# H_bridge.net
KiCad netlist of a schematic drawn in Altium Designer
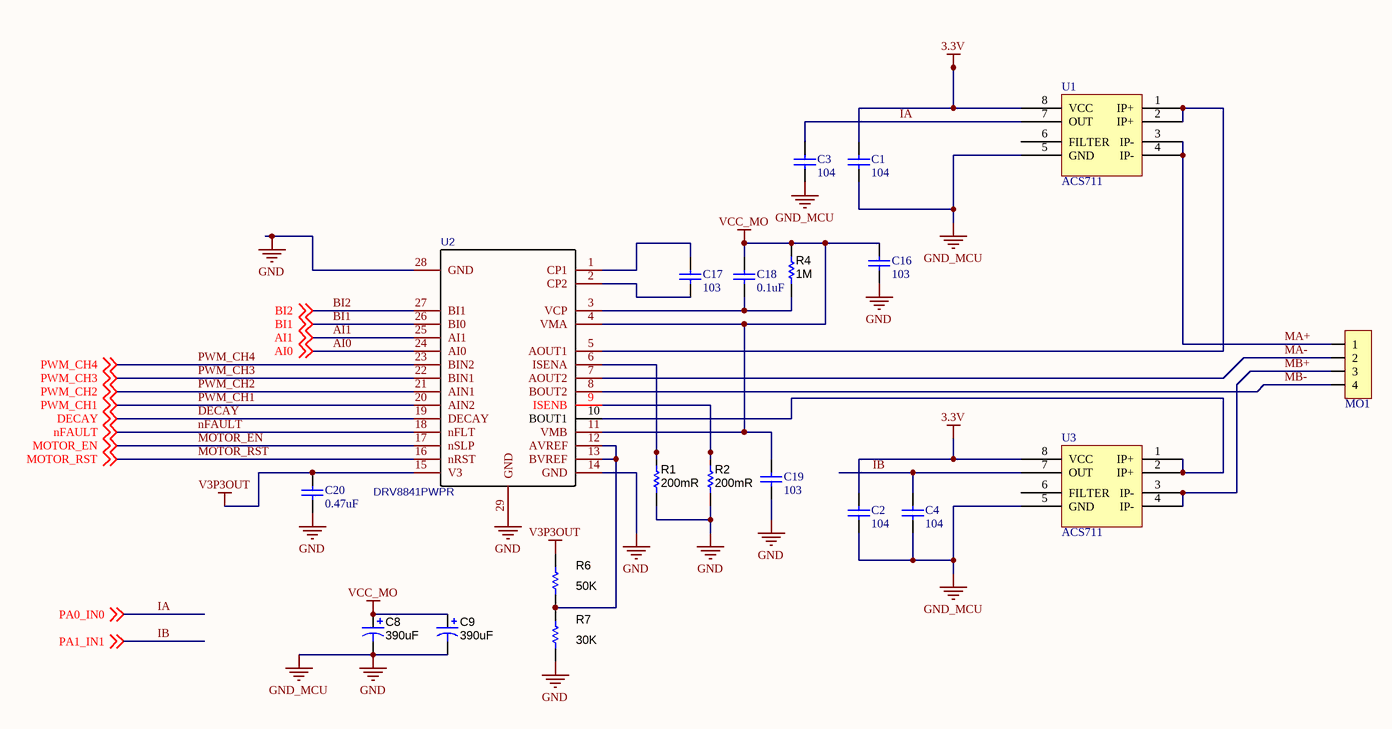
[diagram p0: H_bridge.SchDoc]

(export (version "E")
  (design (tool "Eeschema 10.0.6"))
  (components
    (comp (ref "C1")
      (value "104")
      (footprint "0805_HV")
      (description "Ceramic Chip Capacitor - Standard")
      (fields (field (name "PUBLISHER") "Altium Limited"))
      (libsource (lib "mySch") (part "Capacitor 0805"))
    )
    (comp (ref "C2")
      (value "104")
      (footprint "0805_HV")
      (description "Ceramic Chip Capacitor - Standard")
      (fields (field (name "PUBLISHER") "Altium Limited"))
      (libsource (lib "mySch") (part "Capacitor 0805"))
    )
    (comp (ref "C3")
      (value "104")
      (footprint "0805_HV")
      (description "Ceramic Chip Capacitor - Standard")
      (fields (field (name "PUBLISHER") "Altium Limited"))
      (libsource (lib "mySch") (part "Capacitor 0805"))
    )
    (comp (ref "C4")
      (value "104")
      (footprint "0805_HV")
      (description "Ceramic Chip Capacitor - Standard")
      (fields (field (name "PUBLISHER") "Altium Limited"))
      (libsource (lib "mySch") (part "Capacitor 0805"))
    )
    (comp (ref "C8")
      (value "390uF")
      (footprint "CP1/3.0")
      (fields
        (field (name "PARTNUMBER") "UHW1H391MPD6")
        (field (name "MANUFACTURER") "Nichicon")
        (field (name "VALUEDISPLAYED") "390uF")
        (field (name "PUBLISHER") "Texas Instruments")
      )
      (libsource (lib "mySch") (part "Capacitor TuHoa"))
    )
    (comp (ref "C9")
      (value "390uF")
      (footprint "CP1/3.0")
      (fields
        (field (name "PARTNUMBER") "UHW1H391MPD6")
        (field (name "MANUFACTURER") "Nichicon")
        (field (name "VALUEDISPLAYED") "390uF")
        (field (name "PUBLISHER") "Texas Instruments")
      )
      (libsource (lib "mySch") (part "Capacitor TuHoa"))
    )
    (comp (ref "C16")
      (value "103")
      (footprint "0805_HV")
      (description "Ceramic Chip Capacitor - Standard")
      (fields (field (name "PUBLISHER") "Altium Limited"))
      (libsource (lib "mySch") (part "Capacitor 0805"))
    )
    (comp (ref "C17")
      (value "103")
      (footprint "0805_HV")
      (description "Ceramic Chip Capacitor - Standard")
      (fields (field (name "PUBLISHER") "Altium Limited"))
      (libsource (lib "mySch") (part "Capacitor 0805"))
    )
    (comp (ref "C18")
      (value "0.1uF")
      (footprint "0805_HV")
      (description "Ceramic Chip Capacitor - Standard")
      (fields (field (name "PUBLISHER") "Altium Limited"))
      (libsource (lib "mySch") (part "Capacitor 0805"))
    )
    (comp (ref "C19")
      (value "103")
      (footprint "0805_HV")
      (description "Ceramic Chip Capacitor - Standard")
      (fields (field (name "PUBLISHER") "Altium Limited"))
      (libsource (lib "mySch") (part "Capacitor 0805"))
    )
    (comp (ref "C20")
      (value "0.47uF")
      (footprint "0805_HV")
      (description "Ceramic Chip Capacitor - Standard")
      (fields (field (name "PUBLISHER") "Altium Limited"))
      (libsource (lib "mySch") (part "Capacitor 0805"))
    )
    (comp (ref "MO1")
      (value "Header 4_MH")
      (footprint "HEADER 4")
      (description "Header 4P XH2.54 thẳng")
      (libsource (lib "MH_DA_THU_VIEN_16122016") (part "Header 4_MH"))
    )
    (comp (ref "R1")
      (value "RT0603DRE07140KL")
      (footprint "1210")
      (description "RES, 140 k, 0.5%, 0.1 W, 0603")
      (fields
        (field (name "VALUEDISPLAYED") "200mR")
        (field (name "MANUFACTURER") "Yageo America")
        (field (name "PUBLISHER") "Texas Instruments")
      )
      (libsource (lib "Resistor_0603") (part "RT0603DRE07140KL"))
    )
    (comp (ref "R2")
      (value "RT0603DRE07140KL")
      (footprint "1210")
      (description "RES, 140 k, 0.5%, 0.1 W, 0603")
      (fields
        (field (name "VALUEDISPLAYED") "200mR")
        (field (name "MANUFACTURER") "Yageo America")
        (field (name "PUBLISHER") "Texas Instruments")
      )
      (libsource (lib "Resistor_0603") (part "RT0603DRE07140KL"))
    )
    (comp (ref "R4")
      (value "1M")
      (footprint "0805_HV")
      (description "RES, 100, 1%, 0.1 W, 0402")
      (fields
        (field (name "PARTNUMBER") "ERJ-2RKF1000X")
        (field (name "MANUFACTURER") "Panasonic")
        (field (name "PUBLISHER") "Texas Instruments")
      )
      (libsource (lib "mySch") (part "R nho"))
    )
    (comp (ref "R6")
      (value "50K")
      (footprint "0805_HV")
      (description "RES, 100, 1%, 0.1 W, 0402")
      (fields
        (field (name "PARTNUMBER") "ERJ-2RKF1000X")
        (field (name "MANUFACTURER") "Panasonic")
        (field (name "PUBLISHER") "Texas Instruments")
      )
      (libsource (lib "mySch") (part "R nho"))
    )
    (comp (ref "R7")
      (value "30K")
      (footprint "0805_HV")
      (description "RES, 100, 1%, 0.1 W, 0402")
      (fields
        (field (name "PARTNUMBER") "ERJ-2RKF1000X")
        (field (name "MANUFACTURER") "Panasonic")
        (field (name "PUBLISHER") "Texas Instruments")
      )
      (libsource (lib "mySch") (part "R nho"))
    )
    (comp (ref "U1") (value "ACS711") (footprint "SOP 8") (libsource (lib "mySch") (part "ACS712")))
    (comp (ref "U2")
      (value "DRV8841PWPR")
      (footprint "TSSOP-28EP")
      (fields (field (name "BOM_SUPPLIER PART") "C36542"))
      (libsource (lib "Schlib1") (part "DRV8841PWPR"))
    )
    (comp (ref "U3") (value "ACS711") (footprint "SOP 8") (libsource (lib "mySch") (part "ACS712")))
  )
  (nets
    (net (code "1") (name "/MA+") (class "Default")
      (node (ref "MO1") (pin "1") (pinfunction "1_1") (pintype "passive"))
      (node (ref "U1") (pin "3") (pinfunction "IP-_3") (pintype "passive"))
      (node (ref "U1") (pin "4") (pinfunction "IP-_4") (pintype "passive"))
    )
    (net (code "2") (name "/MA-") (class "Default")
      (node (ref "MO1") (pin "2") (pinfunction "2_2") (pintype "passive"))
      (node (ref "U2") (pin "7") (pinfunction "AOUT2_7") (pintype "passive"))
    )
    (net (code "3") (name "/MB+") (class "Default")
      (node (ref "MO1") (pin "3") (pinfunction "3_3") (pintype "passive"))
      (node (ref "U3") (pin "3") (pinfunction "IP-_3") (pintype "passive"))
      (node (ref "U3") (pin "4") (pinfunction "IP-_4") (pintype "passive"))
    )
    (net (code "4") (name "/MB-") (class "Default")
      (node (ref "MO1") (pin "4") (pinfunction "4_4") (pintype "passive"))
      (node (ref "U2") (pin "8") (pinfunction "BOUT2_8") (pintype "passive"))
    )
    (net (code "5") (name "3.3V") (class "Default")
      (node (ref "C1") (pin "2") (pinfunction "2_2") (pintype "passive"))
      (node (ref "C2") (pin "2") (pinfunction "2_2") (pintype "passive"))
      (node (ref "U1") (pin "8") (pinfunction "VCC_8") (pintype "passive"))
      (node (ref "U3") (pin "8") (pinfunction "VCC_8") (pintype "passive"))
    )
    (net (code "6") (name "AI0") (class "Default")
      (node (ref "U2") (pin "24") (pinfunction "AI0_24") (pintype "passive"))
    )
    (net (code "7") (name "AI1") (class "Default")
      (node (ref "U2") (pin "25") (pinfunction "AI1_25") (pintype "passive"))
    )
    (net (code "8") (name "BI1") (class "Default")
      (node (ref "U2") (pin "26") (pinfunction "BI0_26") (pintype "passive"))
    )
    (net (code "9") (name "BI2") (class "Default")
      (node (ref "U2") (pin "27") (pinfunction "BI1_27") (pintype "passive"))
    )
    (net (code "10") (name "DECAY") (class "Default")
      (node (ref "U2") (pin "19") (pinfunction "DECAY_19") (pintype "passive"))
    )
    (net (code "11") (name "GND") (class "Default")
      (node (ref "C1") (pin "1") (pinfunction "1_1") (pintype "passive"))
      (node (ref "C16") (pin "1") (pinfunction "1_1") (pintype "passive"))
      (node (ref "C19") (pin "1") (pinfunction "1_1") (pintype "passive"))
      (node (ref "C2") (pin "1") (pinfunction "1_1") (pintype "passive"))
      (node (ref "C20") (pin "1") (pinfunction "1_1") (pintype "passive"))
      (node (ref "C3") (pin "1") (pinfunction "1_1") (pintype "passive"))
      (node (ref "C4") (pin "1") (pinfunction "1_1") (pintype "passive"))
      (node (ref "C8") (pin "2") (pinfunction "-_2") (pintype "passive"))
      (node (ref "C9") (pin "2") (pinfunction "-_2") (pintype "passive"))
      (node (ref "R1") (pin "1") (pinfunction "1_1") (pintype "passive"))
      (node (ref "R2") (pin "1") (pinfunction "1_1") (pintype "passive"))
      (node (ref "R7") (pin "1") (pinfunction "1_1") (pintype "passive"))
      (node (ref "U1") (pin "5") (pinfunction "GND_5") (pintype "passive"))
      (node (ref "U2") (pin "14") (pinfunction "GND_14") (pintype "passive"))
      (node (ref "U2") (pin "28") (pinfunction "GND_28") (pintype "passive"))
      (node (ref "U2") (pin "29") (pinfunction "GND_29") (pintype "passive"))
      (node (ref "U3") (pin "5") (pinfunction "GND_5") (pintype "passive"))
    )
    (net (code "12") (name "MOTOR_EN") (class "Default")
      (node (ref "U2") (pin "17") (pinfunction "nSLP_17") (pintype "passive"))
    )
    (net (code "13") (name "MOTOR_RST") (class "Default")
      (node (ref "U2") (pin "16") (pinfunction "nRST_16") (pintype "passive"))
    )
    (net (code "14") (name "Net-(U2-AOUT1)") (class "Default")
      (node (ref "U1") (pin "1") (pinfunction "IP+_1") (pintype "passive"))
      (node (ref "U1") (pin "2") (pinfunction "IP+_2") (pintype "passive"))
      (node (ref "U2") (pin "5") (pinfunction "AOUT1_5") (pintype "passive"))
    )
    (net (code "15") (name "Net-(U2-AVREF)") (class "Default")
      (node (ref "R6") (pin "1") (pinfunction "1_1") (pintype "passive"))
      (node (ref "R7") (pin "2") (pinfunction "2_2") (pintype "passive"))
      (node (ref "U2") (pin "12") (pinfunction "AVREF_12") (pintype "passive"))
      (node (ref "U2") (pin "13") (pinfunction "BVREF_13") (pintype "passive"))
    )
    (net (code "16") (name "Net-(U2-BOUT1)") (class "Default")
      (node (ref "U2") (pin "10") (pinfunction "BOUT1_10") (pintype "passive"))
      (node (ref "U3") (pin "1") (pinfunction "IP+_1") (pintype "passive"))
      (node (ref "U3") (pin "2") (pinfunction "IP+_2") (pintype "passive"))
    )
    (net (code "17") (name "Net-(U2-CP1)") (class "Default")
      (node (ref "C17") (pin "2") (pinfunction "2_2") (pintype "passive"))
      (node (ref "U2") (pin "1") (pinfunction "CP1_1") (pintype "passive"))
    )
    (net (code "18") (name "Net-(U2-CP2)") (class "Default")
      (node (ref "C17") (pin "1") (pinfunction "1_1") (pintype "passive"))
      (node (ref "U2") (pin "2") (pinfunction "CP2_2") (pintype "passive"))
    )
    (net (code "19") (name "Net-(U2-ISENA)") (class "Default")
      (node (ref "R1") (pin "2") (pinfunction "2_2") (pintype "passive"))
      (node (ref "U2") (pin "6") (pinfunction "ISENA_6") (pintype "passive"))
    )
    (net (code "20") (name "Net-(U2-ISENB)") (class "Default")
      (node (ref "R2") (pin "2") (pinfunction "2_2") (pintype "passive"))
      (node (ref "U2") (pin "9") (pinfunction "ISENB_9") (pintype "passive"))
    )
    (net (code "21") (name "Net-(U2-VCP)") (class "Default")
      (node (ref "C18") (pin "1") (pinfunction "1_1") (pintype "passive"))
      (node (ref "R4") (pin "1") (pinfunction "1_1") (pintype "passive"))
      (node (ref "U2") (pin "3") (pinfunction "VCP_3") (pintype "passive"))
    )
    (net (code "22") (name "PA0_IN0") (class "Default")
      (node (ref "C3") (pin "2") (pinfunction "2_2") (pintype "passive"))
      (node (ref "U1") (pin "7") (pinfunction "OUT_7") (pintype "passive"))
    )
    (net (code "23") (name "PA1_IN1") (class "Default")
      (node (ref "C4") (pin "2") (pinfunction "2_2") (pintype "passive"))
      (node (ref "U3") (pin "7") (pinfunction "OUT_7") (pintype "passive"))
    )
    (net (code "24") (name "PWM_CH1") (class "Default")
      (node (ref "U2") (pin "20") (pinfunction "AIN2_20") (pintype "passive"))
    )
    (net (code "25") (name "PWM_CH2") (class "Default")
      (node (ref "U2") (pin "21") (pinfunction "AIN1_21") (pintype "passive"))
    )
    (net (code "26") (name "PWM_CH3") (class "Default")
      (node (ref "U2") (pin "22") (pinfunction "BIN1_22") (pintype "passive"))
    )
    (net (code "27") (name "PWM_CH4") (class "Default")
      (node (ref "U2") (pin "23") (pinfunction "BIN2_23") (pintype "passive"))
    )
    (net (code "28") (name "V3P3OUT") (class "Default")
      (node (ref "C20") (pin "2") (pinfunction "2_2") (pintype "passive"))
      (node (ref "R6") (pin "2") (pinfunction "2_2") (pintype "passive"))
      (node (ref "U2") (pin "15") (pinfunction "V3_15") (pintype "passive"))
    )
    (net (code "29") (name "VCC_MO") (class "Default")
      (node (ref "C16") (pin "2") (pinfunction "2_2") (pintype "passive"))
      (node (ref "C18") (pin "2") (pinfunction "2_2") (pintype "passive"))
      (node (ref "C19") (pin "2") (pinfunction "2_2") (pintype "passive"))
      (node (ref "C8") (pin "1") (pinfunction "+_1") (pintype "passive"))
      (node (ref "C9") (pin "1") (pinfunction "+_1") (pintype "passive"))
      (node (ref "R4") (pin "2") (pinfunction "2_2") (pintype "passive"))
      (node (ref "U2") (pin "11") (pinfunction "VMB_11") (pintype "passive"))
      (node (ref "U2") (pin "4") (pinfunction "VMA_4") (pintype "passive"))
    )
    (net (code "30") (name "nFAULT") (class "Default")
      (node (ref "U2") (pin "18") (pinfunction "nFLT_18") (pintype "passive"))
    )
    (net (code "31") (name "unconnected-(U1-FILTER-Pad6)") (class "Default")
      (node (ref "U1") (pin "6") (pinfunction "FILTER_6") (pintype "passive"))
    )
    (net (code "32") (name "unconnected-(U3-FILTER-Pad6)") (class "Default")
      (node (ref "U3") (pin "6") (pinfunction "FILTER_6") (pintype "passive"))
    )
  )
)
